# Audio_panel_board_for_10_4_inch_panel_wi.net
KiCad netlist of a schematic drawn in EAGLE
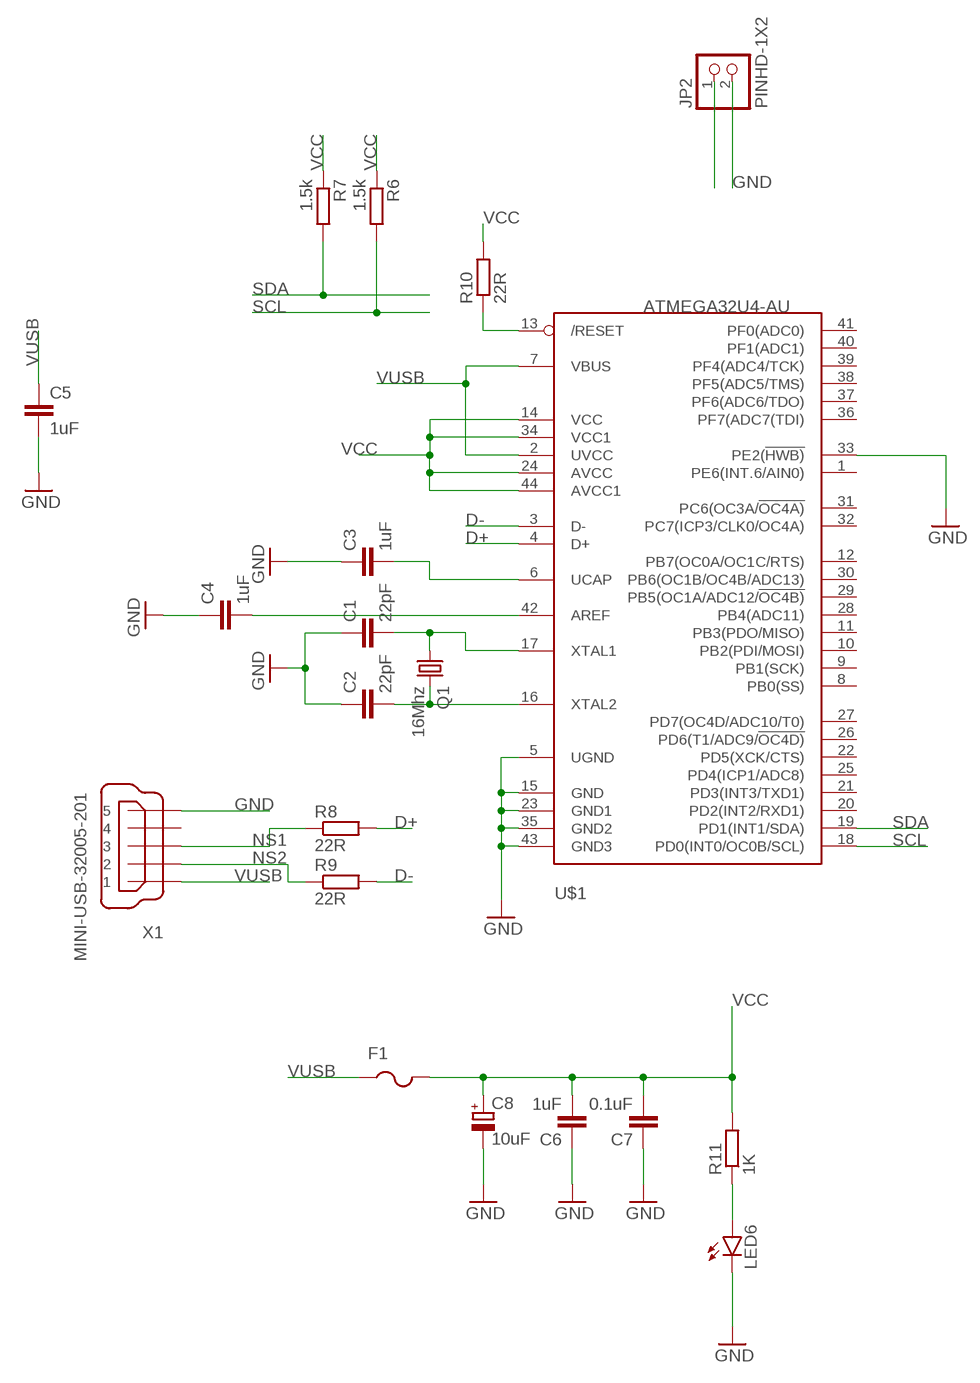
[diagram p0: schematic, sheet 1]

(export (version "E")
  (design (tool "Eeschema 10.0.6"))
  (components
    (comp (ref "C1")
      (value "22pF")
      (footprint "eagle-import:C025-025X050")
      (libsource (lib "eagle-import") (part "C-EU025-025X050"))
    )
    (comp (ref "C2")
      (value "22pF")
      (footprint "eagle-import:C025-025X050")
      (libsource (lib "eagle-import") (part "C-EU025-025X050"))
    )
    (comp (ref "C3")
      (value "1uF")
      (footprint "eagle-import:C025-025X050")
      (libsource (lib "eagle-import") (part "C-EU025-025X050"))
    )
    (comp (ref "C4")
      (value "1uF")
      (footprint "eagle-import:C025-025X050")
      (libsource (lib "eagle-import") (part "C-EU025-025X050"))
    )
    (comp (ref "C5")
      (value "1uF")
      (footprint "eagle-import:C025-025X050")
      (libsource (lib "eagle-import") (part "C-EU025-025X050"))
    )
    (comp (ref "C6")
      (value "1uF")
      (footprint "eagle-import:C025-025X050")
      (libsource (lib "eagle-import") (part "C-EU025-025X050"))
    )
    (comp (ref "C7")
      (value "0.1uF")
      (footprint "eagle-import:C025-025X050")
      (libsource (lib "eagle-import") (part "C-EU025-025X050"))
    )
    (comp (ref "C8")
      (value "10uF")
      (footprint "eagle-import:E2,5-7")
      (libsource (lib "eagle-import") (part "CPOL-EUE2.5-7"))
    )
    (comp (ref "F1")
      (value "PTCFUSE-1206")
      (footprint "eagle-import:R1206")
      (libsource (lib "eagle-import") (part "PTCFUSE-1206"))
    )
    (comp (ref "JP2")
      (value "PINHD-1X2")
      (footprint "eagle-import:1X02")
      (libsource (lib "eagle-import") (part "PINHD-1X2"))
    )
    (comp (ref "LED6")
      (value "LEDCHIP-LED0805")
      (footprint "eagle-import:CHIP-LED0805")
      (libsource (lib "eagle-import") (part "LEDCHIP-LED0805"))
    )
    (comp (ref "Q1")
      (value "16Mhz")
      (footprint "eagle-import:HC49_S")
      (libsource (lib "eagle-import") (part "CRYSTALHC49S"))
    )
    (comp (ref "R6")
      (value "1.5k")
      (footprint "eagle-import:R0805")
      (libsource (lib "eagle-import") (part "R-EU_R0805"))
    )
    (comp (ref "R7")
      (value "1.5k")
      (footprint "eagle-import:R0805")
      (libsource (lib "eagle-import") (part "R-EU_R0805"))
    )
    (comp (ref "R8")
      (value "22R")
      (footprint "eagle-import:R0805")
      (libsource (lib "eagle-import") (part "R-EU_R0805"))
    )
    (comp (ref "R9")
      (value "22R")
      (footprint "eagle-import:R0805")
      (libsource (lib "eagle-import") (part "R-EU_R0805"))
    )
    (comp (ref "R10")
      (value "22R")
      (footprint "eagle-import:R0805")
      (libsource (lib "eagle-import") (part "R-EU_R0805"))
    )
    (comp (ref "R11")
      (value "1K")
      (footprint "eagle-import:R0805")
      (libsource (lib "eagle-import") (part "R-EU_R0805"))
    )
    (comp (ref "U$1")
      (value "ATMEGA32U4-AU")
      (footprint "eagle-import:TQFP44")
      (libsource (lib "eagle-import") (part "ATMEGA32U4-AU"))
    )
    (comp (ref "X1")
      (value "MINI-USB-32005-201")
      (footprint "eagle-import:32005-201")
      (libsource (lib "eagle-import") (part "MINI-USB-32005-201"))
    )
  )
  (nets
    (net (code "1") (name "/D+") (class "Default")
      (node (ref "R8") (pin "2") (pinfunction "2_2") (pintype "passive"))
      (node (ref "U$1") (pin "4") (pinfunction "D+_4") (pintype "bidirectional"))
    )
    (net (code "2") (name "/D-") (class "Default")
      (node (ref "R9") (pin "2") (pinfunction "2_2") (pintype "passive"))
      (node (ref "U$1") (pin "3") (pinfunction "D-_3") (pintype "bidirectional"))
    )
    (net (code "3") (name "/NS1") (class "Default")
      (node (ref "R8") (pin "1") (pinfunction "1_1") (pintype "passive"))
      (node (ref "X1") (pin "3") (pinfunction "3_3") (pintype "passive"))
    )
    (net (code "4") (name "/NS2") (class "Default")
      (node (ref "R9") (pin "1") (pinfunction "1_1") (pintype "passive"))
      (node (ref "X1") (pin "2") (pinfunction "2_2") (pintype "passive"))
    )
    (net (code "5") (name "/SCL") (class "Default")
      (node (ref "R6") (pin "2") (pinfunction "2_2") (pintype "passive"))
      (node (ref "U$1") (pin "18") (pinfunction "PD0(INT0/OC0B/SCL)_18") (pintype "bidirectional"))
    )
    (net (code "6") (name "/SDA") (class "Default")
      (node (ref "R7") (pin "2") (pinfunction "2_2") (pintype "passive"))
      (node (ref "U$1") (pin "19") (pinfunction "PD1(INT1/SDA)_19") (pintype "bidirectional"))
    )
    (net (code "7") (name "/VCC") (class "Default")
      (node (ref "C6") (pin "2") (pinfunction "2_2") (pintype "passive"))
      (node (ref "C7") (pin "2") (pinfunction "2_2") (pintype "passive"))
      (node (ref "C8") (pin "+") (pinfunction "+_+") (pintype "passive"))
      (node (ref "F1") (pin "2") (pinfunction "2_2") (pintype "passive"))
      (node (ref "R10") (pin "2") (pinfunction "2_2") (pintype "passive"))
      (node (ref "R11") (pin "2") (pinfunction "2_2") (pintype "passive"))
      (node (ref "R6") (pin "1") (pinfunction "1_1") (pintype "passive"))
      (node (ref "R7") (pin "1") (pinfunction "1_1") (pintype "passive"))
      (node (ref "U$1") (pin "14") (pinfunction "VCC_14") (pintype "bidirectional"))
      (node (ref "U$1") (pin "24") (pinfunction "AVCC_24") (pintype "bidirectional"))
      (node (ref "U$1") (pin "34") (pinfunction "VCC1_34") (pintype "bidirectional"))
      (node (ref "U$1") (pin "44") (pinfunction "AVCC1_44") (pintype "bidirectional"))
    )
    (net (code "8") (name "/VUSB") (class "Default")
      (node (ref "C5") (pin "1") (pinfunction "1_1") (pintype "passive"))
      (node (ref "F1") (pin "1") (pinfunction "1_1") (pintype "passive"))
      (node (ref "U$1") (pin "2") (pinfunction "UVCC_2") (pintype "bidirectional"))
      (node (ref "U$1") (pin "7") (pinfunction "VBUS_7") (pintype "bidirectional"))
      (node (ref "X1") (pin "1") (pinfunction "1_1") (pintype "passive"))
    )
    (net (code "9") (name "GND") (class "Default")
      (node (ref "C1") (pin "1") (pinfunction "1_1") (pintype "passive"))
      (node (ref "C2") (pin "1") (pinfunction "1_1") (pintype "passive"))
      (node (ref "C3") (pin "1") (pinfunction "1_1") (pintype "passive"))
      (node (ref "C4") (pin "1") (pinfunction "1_1") (pintype "passive"))
      (node (ref "C5") (pin "2") (pinfunction "2_2") (pintype "passive"))
      (node (ref "C6") (pin "1") (pinfunction "1_1") (pintype "passive"))
      (node (ref "C7") (pin "1") (pinfunction "1_1") (pintype "passive"))
      (node (ref "C8") (pin "-") (pinfunction "-_-") (pintype "passive"))
      (node (ref "JP2") (pin "2") (pinfunction "2_2") (pintype "passive"))
      (node (ref "LED6") (pin "C") (pinfunction "C_C") (pintype "passive"))
      (node (ref "U$1") (pin "15") (pinfunction "GND_15") (pintype "bidirectional"))
      (node (ref "U$1") (pin "23") (pinfunction "GND1_23") (pintype "bidirectional"))
      (node (ref "U$1") (pin "33") (pinfunction "PE2(~{HWB})_33") (pintype "bidirectional"))
      (node (ref "U$1") (pin "35") (pinfunction "GND2_35") (pintype "bidirectional"))
      (node (ref "U$1") (pin "43") (pinfunction "GND3_43") (pintype "bidirectional"))
      (node (ref "U$1") (pin "5") (pinfunction "UGND_5") (pintype "bidirectional"))
      (node (ref "X1") (pin "5") (pinfunction "5_5") (pintype "passive"))
    )
    (net (code "10") (name "Net-(LED6-PadA)") (class "Default")
      (node (ref "LED6") (pin "A") (pinfunction "A_A") (pintype "passive"))
      (node (ref "R11") (pin "1") (pinfunction "1_1") (pintype "passive"))
    )
    (net (code "11") (name "Net-(U$1-AREF)") (class "Default")
      (node (ref "C4") (pin "2") (pinfunction "2_2") (pintype "passive"))
      (node (ref "U$1") (pin "42") (pinfunction "AREF_42") (pintype "bidirectional"))
    )
    (net (code "12") (name "Net-(U$1-UCAP)") (class "Default")
      (node (ref "C3") (pin "2") (pinfunction "2_2") (pintype "passive"))
      (node (ref "U$1") (pin "6") (pinfunction "UCAP_6") (pintype "bidirectional"))
    )
    (net (code "13") (name "Net-(U$1-XTAL1)") (class "Default")
      (node (ref "C1") (pin "2") (pinfunction "2_2") (pintype "passive"))
      (node (ref "Q1") (pin "1") (pinfunction "1_1") (pintype "passive"))
      (node (ref "U$1") (pin "17") (pinfunction "XTAL1_17") (pintype "bidirectional"))
    )
    (net (code "14") (name "Net-(U$1-XTAL2)") (class "Default")
      (node (ref "C2") (pin "2") (pinfunction "2_2") (pintype "passive"))
      (node (ref "Q1") (pin "2") (pinfunction "2_2") (pintype "passive"))
      (node (ref "U$1") (pin "16") (pinfunction "XTAL2_16") (pintype "bidirectional"))
    )
    (net (code "15") (name "Net-(U$1-{slash}RESET)") (class "Default")
      (node (ref "R10") (pin "1") (pinfunction "1_1") (pintype "passive"))
      (node (ref "U$1") (pin "13") (pinfunction "/RESET_13") (pintype "bidirectional"))
    )
    (net (code "16") (name "unconnected-(JP2-Pad1)") (class "Default")
      (node (ref "JP2") (pin "1") (pinfunction "1_1") (pintype "passive"))
    )
    (net (code "17") (name "unconnected-(U$1-PB0(SS)-Pad8)") (class "Default")
      (node (ref "U$1") (pin "8") (pinfunction "PB0(SS)_8") (pintype "bidirectional"))
    )
    (net (code "18") (name "unconnected-(U$1-PB1(SCK)-Pad9)") (class "Default")
      (node (ref "U$1") (pin "9") (pinfunction "PB1(SCK)_9") (pintype "bidirectional"))
    )
    (net (code "19") (name "unconnected-(U$1-PB2(PDI{slash}MOSI)-Pad10)") (class "Default")
      (node (ref "U$1") (pin "10") (pinfunction "PB2(PDI/MOSI)_10") (pintype "bidirectional"))
    )
    (net (code "20") (name "unconnected-(U$1-PB3(PDO{slash}MISO)-Pad11)") (class "Default")
      (node (ref "U$1") (pin "11") (pinfunction "PB3(PDO/MISO)_11") (pintype "bidirectional"))
    )
    (net (code "21") (name "unconnected-(U$1-PB4(ADC11)-Pad28)") (class "Default")
      (node (ref "U$1") (pin "28") (pinfunction "PB4(ADC11)_28") (pintype "bidirectional"))
    )
    (net (code "22") (name "unconnected-(U$1-PB5(OC1A{slash}ADC12{slash}~{OC4B})-Pad29)") (class "Default")
      (node (ref "U$1") (pin "29") (pinfunction "PB5(OC1A/ADC12/~{OC4B})_29") (pintype "bidirectional"))
    )
    (net (code "23") (name "unconnected-(U$1-PB6(OC1B{slash}OC4B{slash}ADC13)-Pad30)") (class "Default")
      (node (ref "U$1") (pin "30") (pinfunction "PB6(OC1B/OC4B/ADC13)_30") (pintype "bidirectional"))
    )
    (net (code "24") (name "unconnected-(U$1-PB7(OC0A{slash}OC1C{slash}RTS)-Pad12)") (class "Default")
      (node (ref "U$1") (pin "12") (pinfunction "PB7(OC0A/OC1C/RTS)_12") (pintype "bidirectional"))
    )
    (net (code "25") (name "unconnected-(U$1-PC6(OC3A{slash}~{OC4A})-Pad31)") (class "Default")
      (node (ref "U$1") (pin "31") (pinfunction "PC6(OC3A/~{OC4A})_31") (pintype "bidirectional"))
    )
    (net (code "26") (name "unconnected-(U$1-PC7(ICP3{slash}CLK0{slash}OC4A)-Pad32)") (class "Default")
      (node (ref "U$1") (pin "32") (pinfunction "PC7(ICP3/CLK0/OC4A)_32") (pintype "bidirectional"))
    )
    (net (code "27") (name "unconnected-(U$1-PD2(INT2{slash}RXD1)-Pad20)") (class "Default")
      (node (ref "U$1") (pin "20") (pinfunction "PD2(INT2/RXD1)_20") (pintype "bidirectional"))
    )
    (net (code "28") (name "unconnected-(U$1-PD3(INT3{slash}TXD1)-Pad21)") (class "Default")
      (node (ref "U$1") (pin "21") (pinfunction "PD3(INT3/TXD1)_21") (pintype "bidirectional"))
    )
    (net (code "29") (name "unconnected-(U$1-PD4(ICP1{slash}ADC8)-Pad25)") (class "Default")
      (node (ref "U$1") (pin "25") (pinfunction "PD4(ICP1/ADC8)_25") (pintype "bidirectional"))
    )
    (net (code "30") (name "unconnected-(U$1-PD5(XCK{slash}CTS)-Pad22)") (class "Default")
      (node (ref "U$1") (pin "22") (pinfunction "PD5(XCK/CTS)_22") (pintype "bidirectional"))
    )
    (net (code "31") (name "unconnected-(U$1-PD6(T1{slash}ADC9{slash}~{OC4D})-Pad26)") (class "Default")
      (node (ref "U$1") (pin "26") (pinfunction "PD6(T1/ADC9/~{OC4D})_26") (pintype "bidirectional"))
    )
    (net (code "32") (name "unconnected-(U$1-PD7(OC4D{slash}ADC10{slash}T0)-Pad27)") (class "Default")
      (node (ref "U$1") (pin "27") (pinfunction "PD7(OC4D/ADC10/T0)_27") (pintype "bidirectional"))
    )
    (net (code "33") (name "unconnected-(U$1-PE6(INT.6{slash}AIN0)-Pad1)") (class "Default")
      (node (ref "U$1") (pin "1") (pinfunction "PE6(INT.6/AIN0)_1") (pintype "bidirectional"))
    )
    (net (code "34") (name "unconnected-(U$1-PF0(ADC0)-Pad41)") (class "Default")
      (node (ref "U$1") (pin "41") (pinfunction "PF0(ADC0)_41") (pintype "bidirectional"))
    )
    (net (code "35") (name "unconnected-(U$1-PF1(ADC1)-Pad40)") (class "Default")
      (node (ref "U$1") (pin "40") (pinfunction "PF1(ADC1)_40") (pintype "bidirectional"))
    )
    (net (code "36") (name "unconnected-(U$1-PF4(ADC4{slash}TCK)-Pad39)") (class "Default")
      (node (ref "U$1") (pin "39") (pinfunction "PF4(ADC4/TCK)_39") (pintype "bidirectional"))
    )
    (net (code "37") (name "unconnected-(U$1-PF5(ADC5{slash}TMS)-Pad38)") (class "Default")
      (node (ref "U$1") (pin "38") (pinfunction "PF5(ADC5/TMS)_38") (pintype "bidirectional"))
    )
    (net (code "38") (name "unconnected-(U$1-PF6(ADC6{slash}TDO)-Pad37)") (class "Default")
      (node (ref "U$1") (pin "37") (pinfunction "PF6(ADC6/TDO)_37") (pintype "bidirectional"))
    )
    (net (code "39") (name "unconnected-(U$1-PF7(ADC7(TDI)-Pad36)") (class "Default")
      (node (ref "U$1") (pin "36") (pinfunction "PF7(ADC7(TDI)_36") (pintype "bidirectional"))
    )
    (net (code "40") (name "unconnected-(X1-Pad4)") (class "Default")
      (node (ref "X1") (pin "4") (pinfunction "4_4") (pintype "passive"))
    )
  )
)
